# LDO_Sheet.net
KiCad netlist of a schematic drawn in Altium Designer
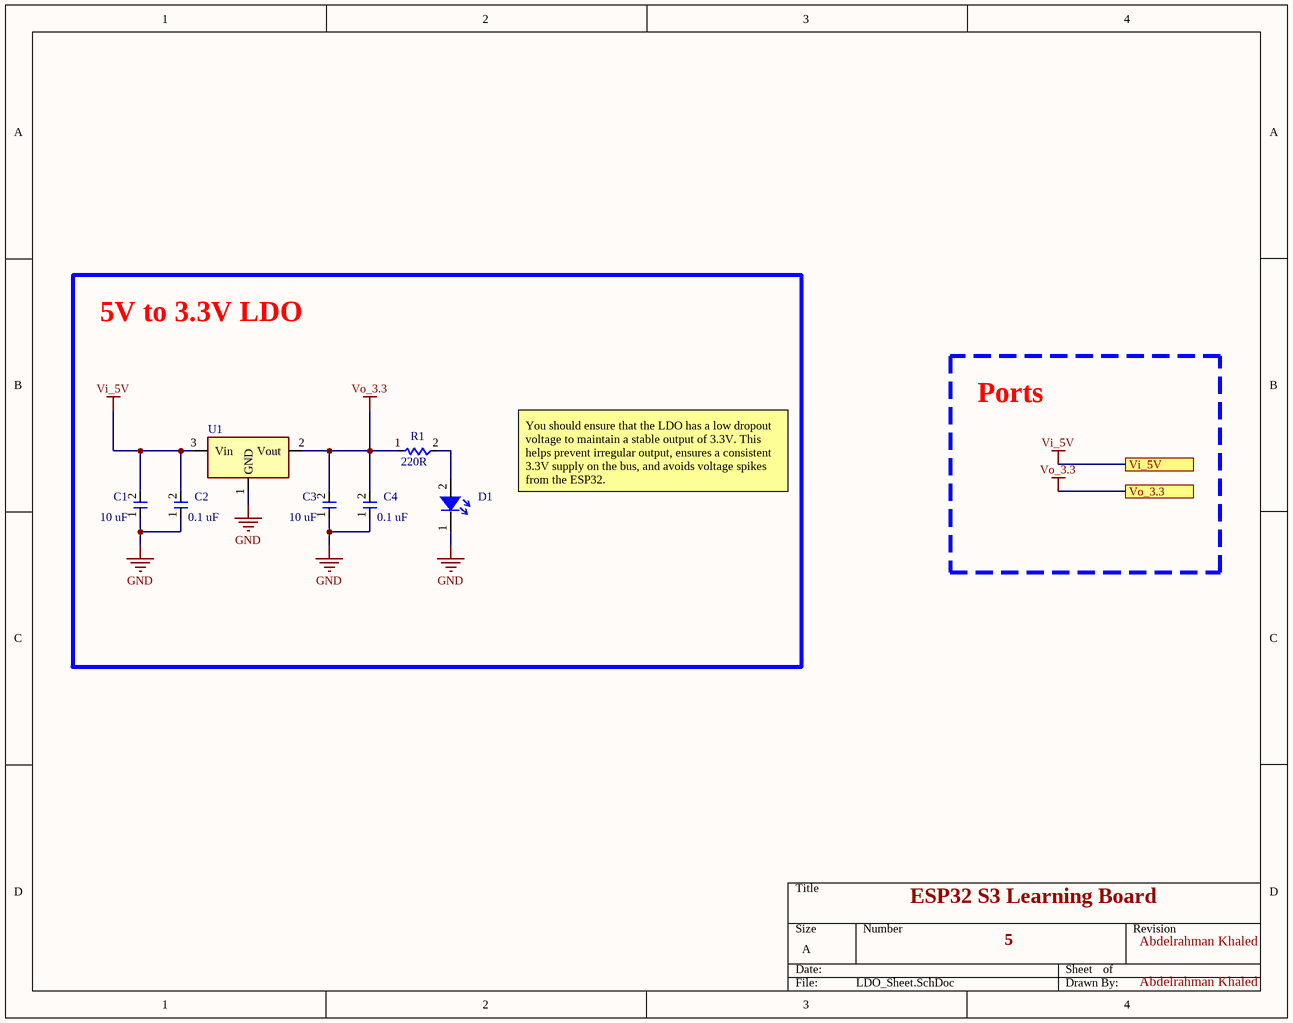
[diagram p0: LDO_Sheet.SchDoc]

(export (version "E")
  (design (tool "Eeschema 10.0.6"))
  (components
    (comp (ref "C1")
      (value "10 uF")
      (footprint "Capacitor")
      (libsource (lib "ESP32_S3_Integrated_Library") (part "Capacitor"))
    )
    (comp (ref "C2")
      (value "0.1 uF")
      (footprint "Capacitor")
      (libsource (lib "ESP32_S3_Integrated_Library") (part "Capacitor"))
    )
    (comp (ref "C3")
      (value "10 uF")
      (footprint "Capacitor")
      (libsource (lib "ESP32_S3_Integrated_Library") (part "Capacitor"))
    )
    (comp (ref "C4")
      (value "0.1 uF")
      (footprint "Capacitor")
      (libsource (lib "ESP32_S3_Integrated_Library") (part "Capacitor"))
    )
    (comp (ref "D1")
      (value "Red Led")
      (footprint "Led")
      (libsource (lib "ESP32_S3_Integrated_Library") (part "LED"))
    )
    (comp (ref "R1")
      (value "220R")
      (footprint "Resistor")
      (libsource (lib "ESP32_S3_Integrated_Library") (part "Resistance"))
    )
    (comp (ref "U1")
      (value "Regulator LDO 3.3V")
      (footprint "Regulator 3.3V")
      (libsource (lib "ESP32_S3_Integrated_Library") (part "Regulator LDO 3.3V"))
    )
  )
  (nets
    (net (code "1") (name "GND") (class "Default")
      (node (ref "C1") (pin "1") (pinfunction "Pin_1_1") (pintype "passive"))
      (node (ref "C2") (pin "1") (pinfunction "Pin_1_1") (pintype "passive"))
      (node (ref "C3") (pin "1") (pinfunction "Pin_1_1") (pintype "passive"))
      (node (ref "C4") (pin "1") (pinfunction "Pin_1_1") (pintype "passive"))
      (node (ref "D1") (pin "1") (pintype "passive"))
      (node (ref "U1") (pin "1") (pinfunction "GND_1") (pintype "passive"))
    )
    (net (code "2") (name "Net-(R1-pin_2)") (class "Default")
      (node (ref "D1") (pin "2") (pintype "passive"))
      (node (ref "R1") (pin "2") (pinfunction "pin_2_2") (pintype "passive"))
    )
    (net (code "3") (name "Vi_5V") (class "Default")
      (node (ref "C1") (pin "2") (pinfunction "Pin_2_2") (pintype "passive"))
      (node (ref "C2") (pin "2") (pinfunction "Pin_2_2") (pintype "passive"))
      (node (ref "U1") (pin "3") (pinfunction "Vin_3") (pintype "passive"))
    )
    (net (code "4") (name "Vo_3.3") (class "Default")
      (node (ref "C3") (pin "2") (pinfunction "Pin_2_2") (pintype "passive"))
      (node (ref "C4") (pin "2") (pinfunction "Pin_2_2") (pintype "passive"))
      (node (ref "R1") (pin "1") (pinfunction "Pin_1_1") (pintype "passive"))
      (node (ref "U1") (pin "2") (pinfunction "Vout_2") (pintype "passive"))
    )
  )
)
